# SCH_PCB3-ROBOTIC-DRA-KIT_2024-08-23_V1_1.net
KiCad netlist of a schematic drawn in EasyEDA
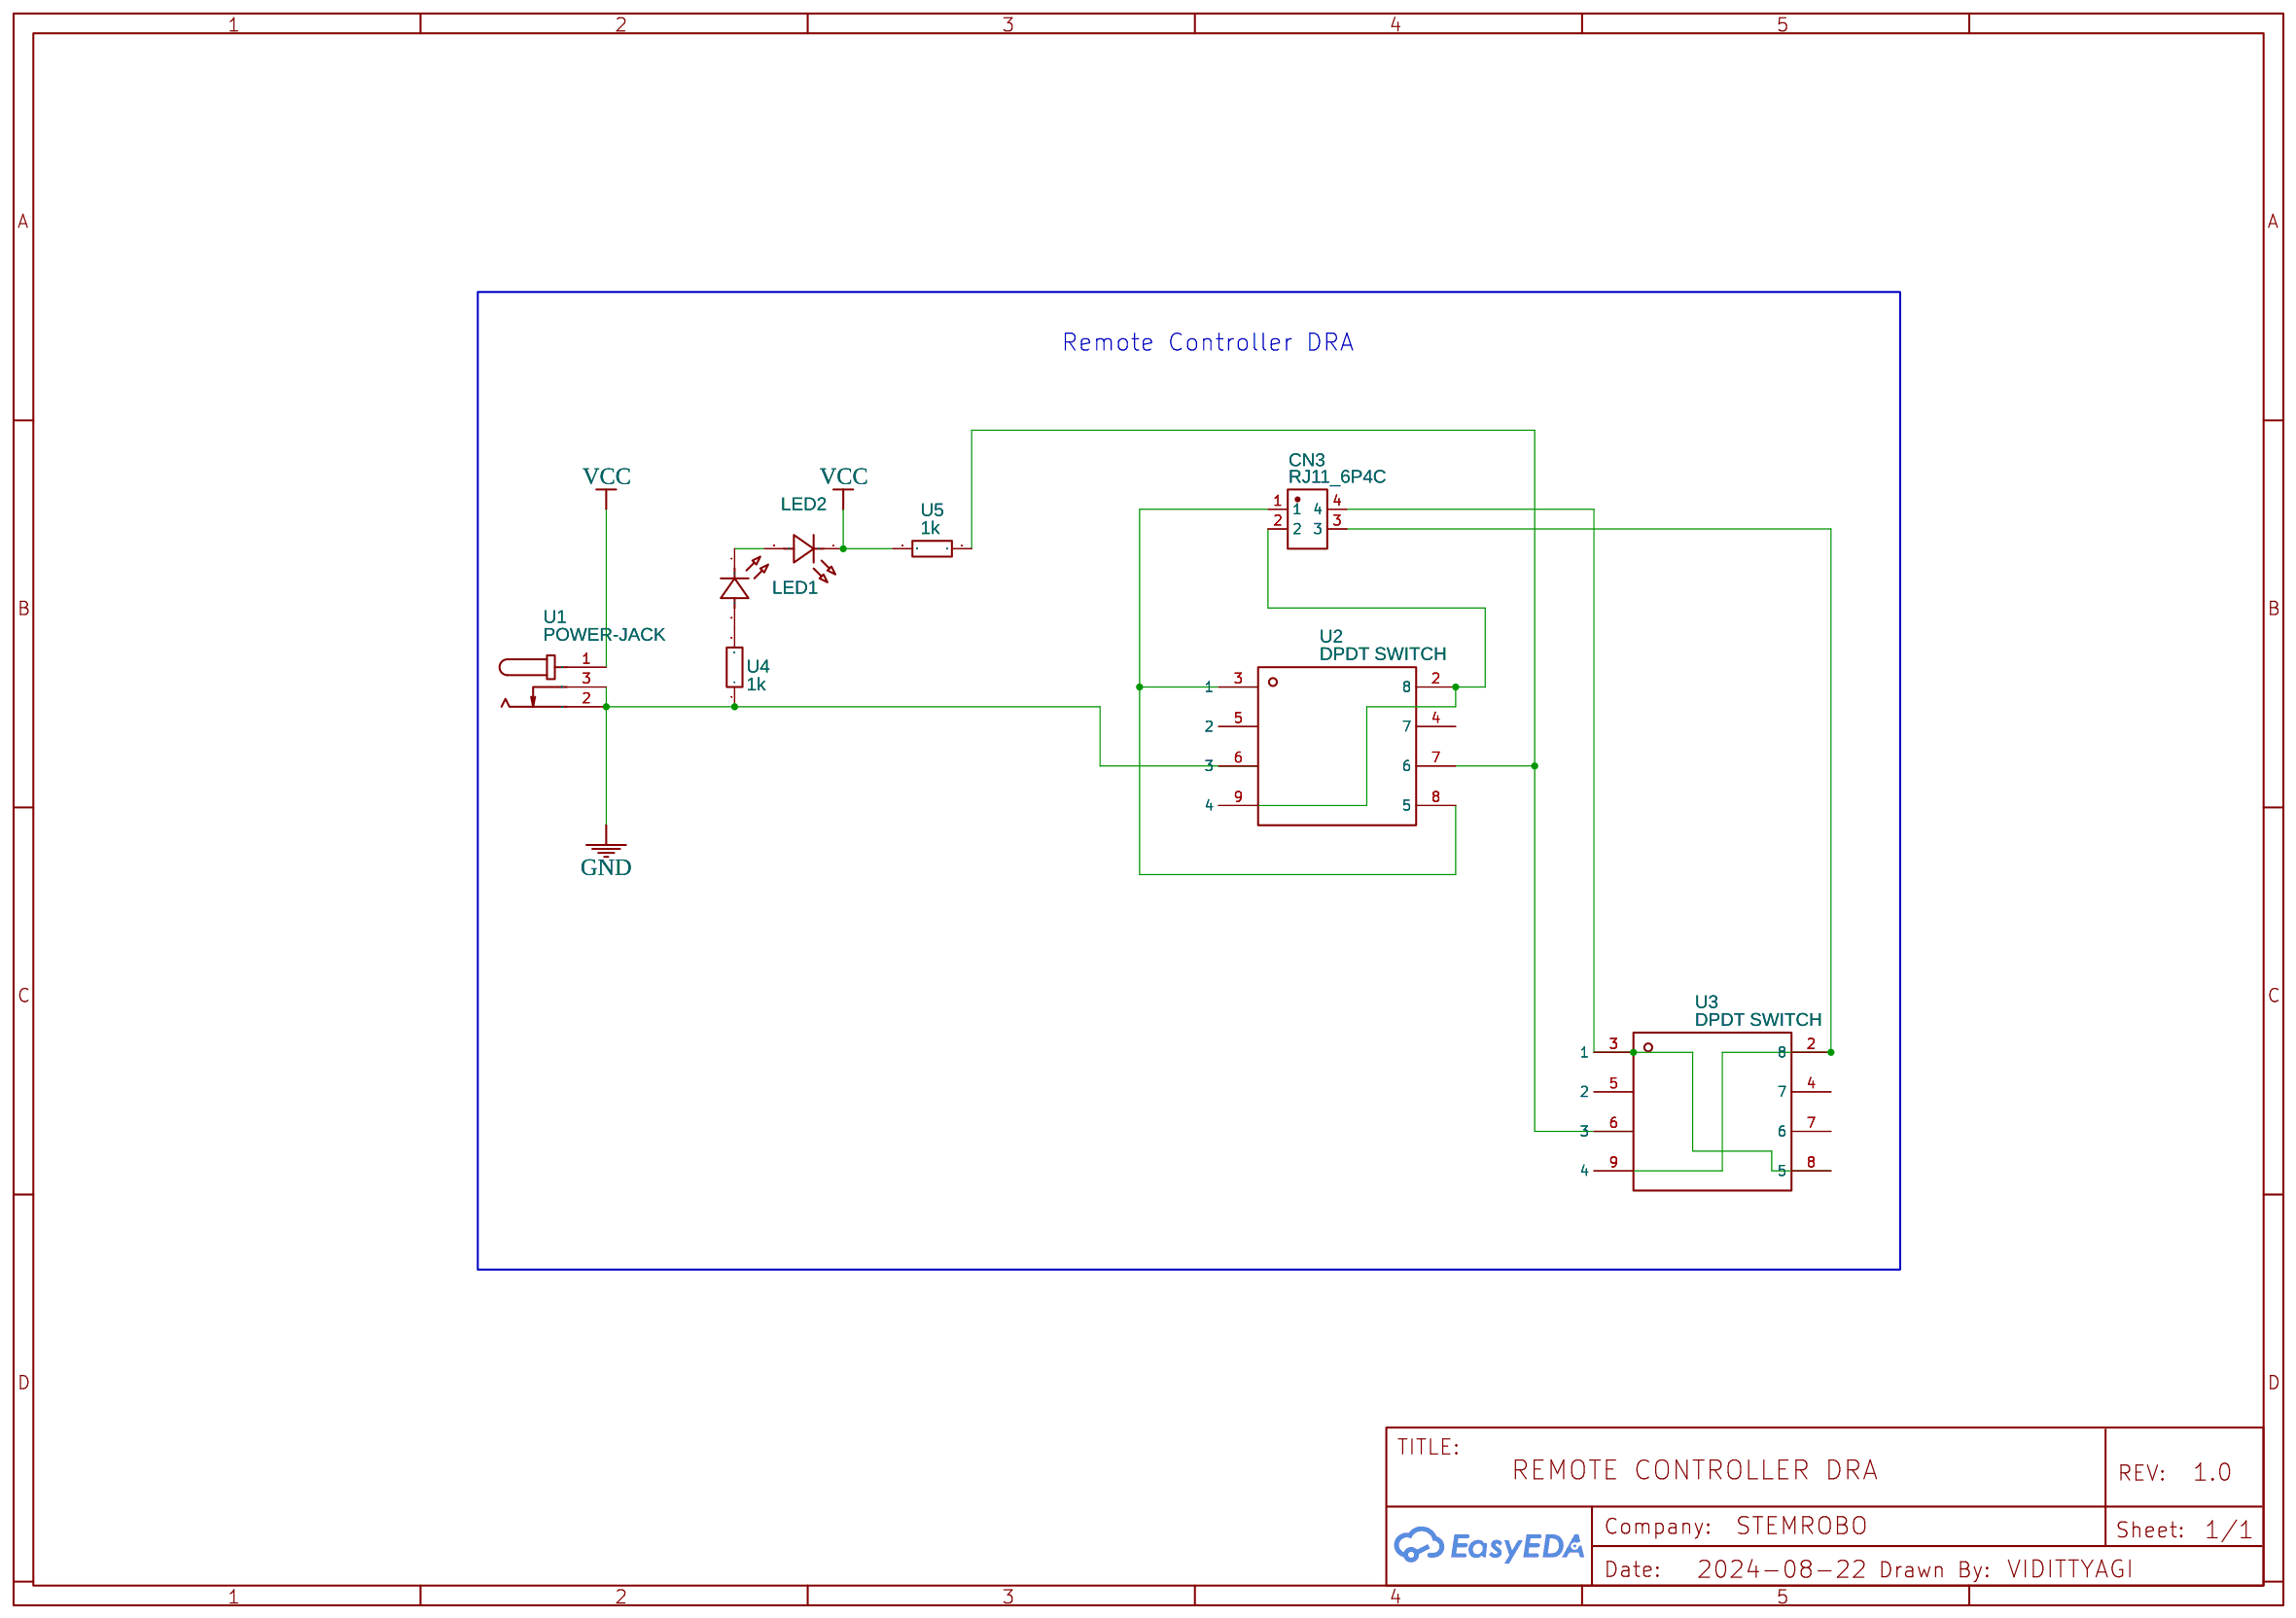
[diagram p0: schematic sheet]

(export (version "E")
  (design (tool "Eeschema 10.0.6"))
  (components
    (comp (ref "CN3") (value "RJ11_6P4C") (libsource (lib "") (part "RJ11_6P4C")))
    (comp (ref "LED1")
      (value "15400394A3590")
      (fields (field (name "Manufacturer") "Wurth(伍尔特)"))
      (libsource (lib "") (part "15400394A3590"))
    )
    (comp (ref "LED2")
      (value "15400394A3590")
      (fields (field (name "Manufacturer") "Wurth(伍尔特)"))
      (libsource (lib "") (part "15400394A3590_1"))
    )
    (comp (ref "U1")
      (value "POWER-JACK")
      (fields (field (name "Manufacturer") "索峰"))
      (libsource (lib "") (part "POWER-JACK"))
    )
    (comp (ref "U2") (value "DPDT SWITCH") (libsource (lib "") (part "DPDT SWITCH")))
    (comp (ref "U3") (value "DPDT SWITCH") (libsource (lib "") (part "DPDT SWITCH")))
    (comp (ref "U4")
      (value "1k")
      (fields (field (name "Manufacturer Part") "CFR1WSJT-52-1K6") (field (name "Manufacturer") "YAGEO(国巨)"))
      (libsource (lib "") (part "CFR1WSJT-52-1K6"))
    )
    (comp (ref "U5")
      (value "1k")
      (fields (field (name "Manufacturer Part") "CFR1WSJT-52-1K6") (field (name "Manufacturer") "YAGEO(国巨)"))
      (libsource (lib "") (part "CFR1WSJT-52-1K6_1"))
    )
  )
  (nets
    (net (code "1") (name "GND") (class "Default")
      (node (ref "U1") (pin "2") (pinfunction "2_2") (pintype "unspecified"))
      (node (ref "U1") (pin "3") (pinfunction "3_3") (pintype "unspecified"))
      (node (ref "U2") (pin "6") (pinfunction "3_6") (pintype "unspecified"))
      (node (ref "U4") (pin "1") (pinfunction "1_1") (pintype "unspecified"))
    )
    (net (code "2") (name "Net-(LED1-A)") (class "Default")
      (node (ref "LED1") (pin "2") (pinfunction "A_2") (pintype "unspecified"))
      (node (ref "U4") (pin "2") (pinfunction "2_2") (pintype "unspecified"))
    )
    (net (code "3") (name "Net-(LED1-K)") (class "Default")
      (node (ref "LED1") (pin "1") (pinfunction "K_1") (pintype "unspecified"))
      (node (ref "LED2") (pin "2") (pinfunction "A_2") (pintype "unspecified"))
    )
    (net (code "4") (name "Net-(U2-1)") (class "Default")
      (node (ref "CN3") (pin "1") (pinfunction "1_1") (pintype "unspecified"))
      (node (ref "U2") (pin "3") (pinfunction "1_3") (pintype "unspecified"))
      (node (ref "U2") (pin "8") (pinfunction "5_8") (pintype "unspecified"))
    )
    (net (code "5") (name "Net-(U2-4)") (class "Default")
      (node (ref "CN3") (pin "2") (pinfunction "2_2") (pintype "unspecified"))
      (node (ref "U2") (pin "2") (pinfunction "8_2") (pintype "unspecified"))
      (node (ref "U2") (pin "9") (pinfunction "4_9") (pintype "unspecified"))
    )
    (net (code "6") (name "Net-(U2-6)") (class "Default")
      (node (ref "U2") (pin "7") (pinfunction "6_7") (pintype "unspecified"))
      (node (ref "U3") (pin "6") (pinfunction "3_6") (pintype "unspecified"))
      (node (ref "U5") (pin "1") (pinfunction "1_1") (pintype "unspecified"))
    )
    (net (code "7") (name "Net-(U3-1)") (class "Default")
      (node (ref "CN3") (pin "4") (pinfunction "4_4") (pintype "unspecified"))
      (node (ref "U3") (pin "3") (pinfunction "1_3") (pintype "unspecified"))
      (node (ref "U3") (pin "8") (pinfunction "5_8") (pintype "unspecified"))
    )
    (net (code "8") (name "Net-(U3-4)") (class "Default")
      (node (ref "CN3") (pin "3") (pinfunction "3_3") (pintype "unspecified"))
      (node (ref "U3") (pin "2") (pinfunction "8_2") (pintype "unspecified"))
      (node (ref "U3") (pin "9") (pinfunction "4_9") (pintype "unspecified"))
    )
    (net (code "9") (name "VCC") (class "Default")
      (node (ref "LED2") (pin "1") (pinfunction "K_1") (pintype "unspecified"))
      (node (ref "U1") (pin "1") (pinfunction "1_1") (pintype "unspecified"))
      (node (ref "U5") (pin "2") (pinfunction "2_2") (pintype "unspecified"))
    )
    (net (code "10") (name "unconnected-(U2-2-Pad5)") (class "Default")
      (node (ref "U2") (pin "5") (pinfunction "2_5") (pintype "unspecified"))
    )
    (net (code "11") (name "unconnected-(U2-7-Pad4)") (class "Default")
      (node (ref "U2") (pin "4") (pinfunction "7_4") (pintype "unspecified"))
    )
    (net (code "12") (name "unconnected-(U3-2-Pad5)") (class "Default")
      (node (ref "U3") (pin "5") (pinfunction "2_5") (pintype "unspecified"))
    )
    (net (code "13") (name "unconnected-(U3-6-Pad7)") (class "Default")
      (node (ref "U3") (pin "7") (pinfunction "6_7") (pintype "unspecified"))
    )
    (net (code "14") (name "unconnected-(U3-7-Pad4)") (class "Default")
      (node (ref "U3") (pin "4") (pinfunction "7_4") (pintype "unspecified"))
    )
  )
)
